# R602X.net
KiCad netlist of a schematic drawn in EAGLE
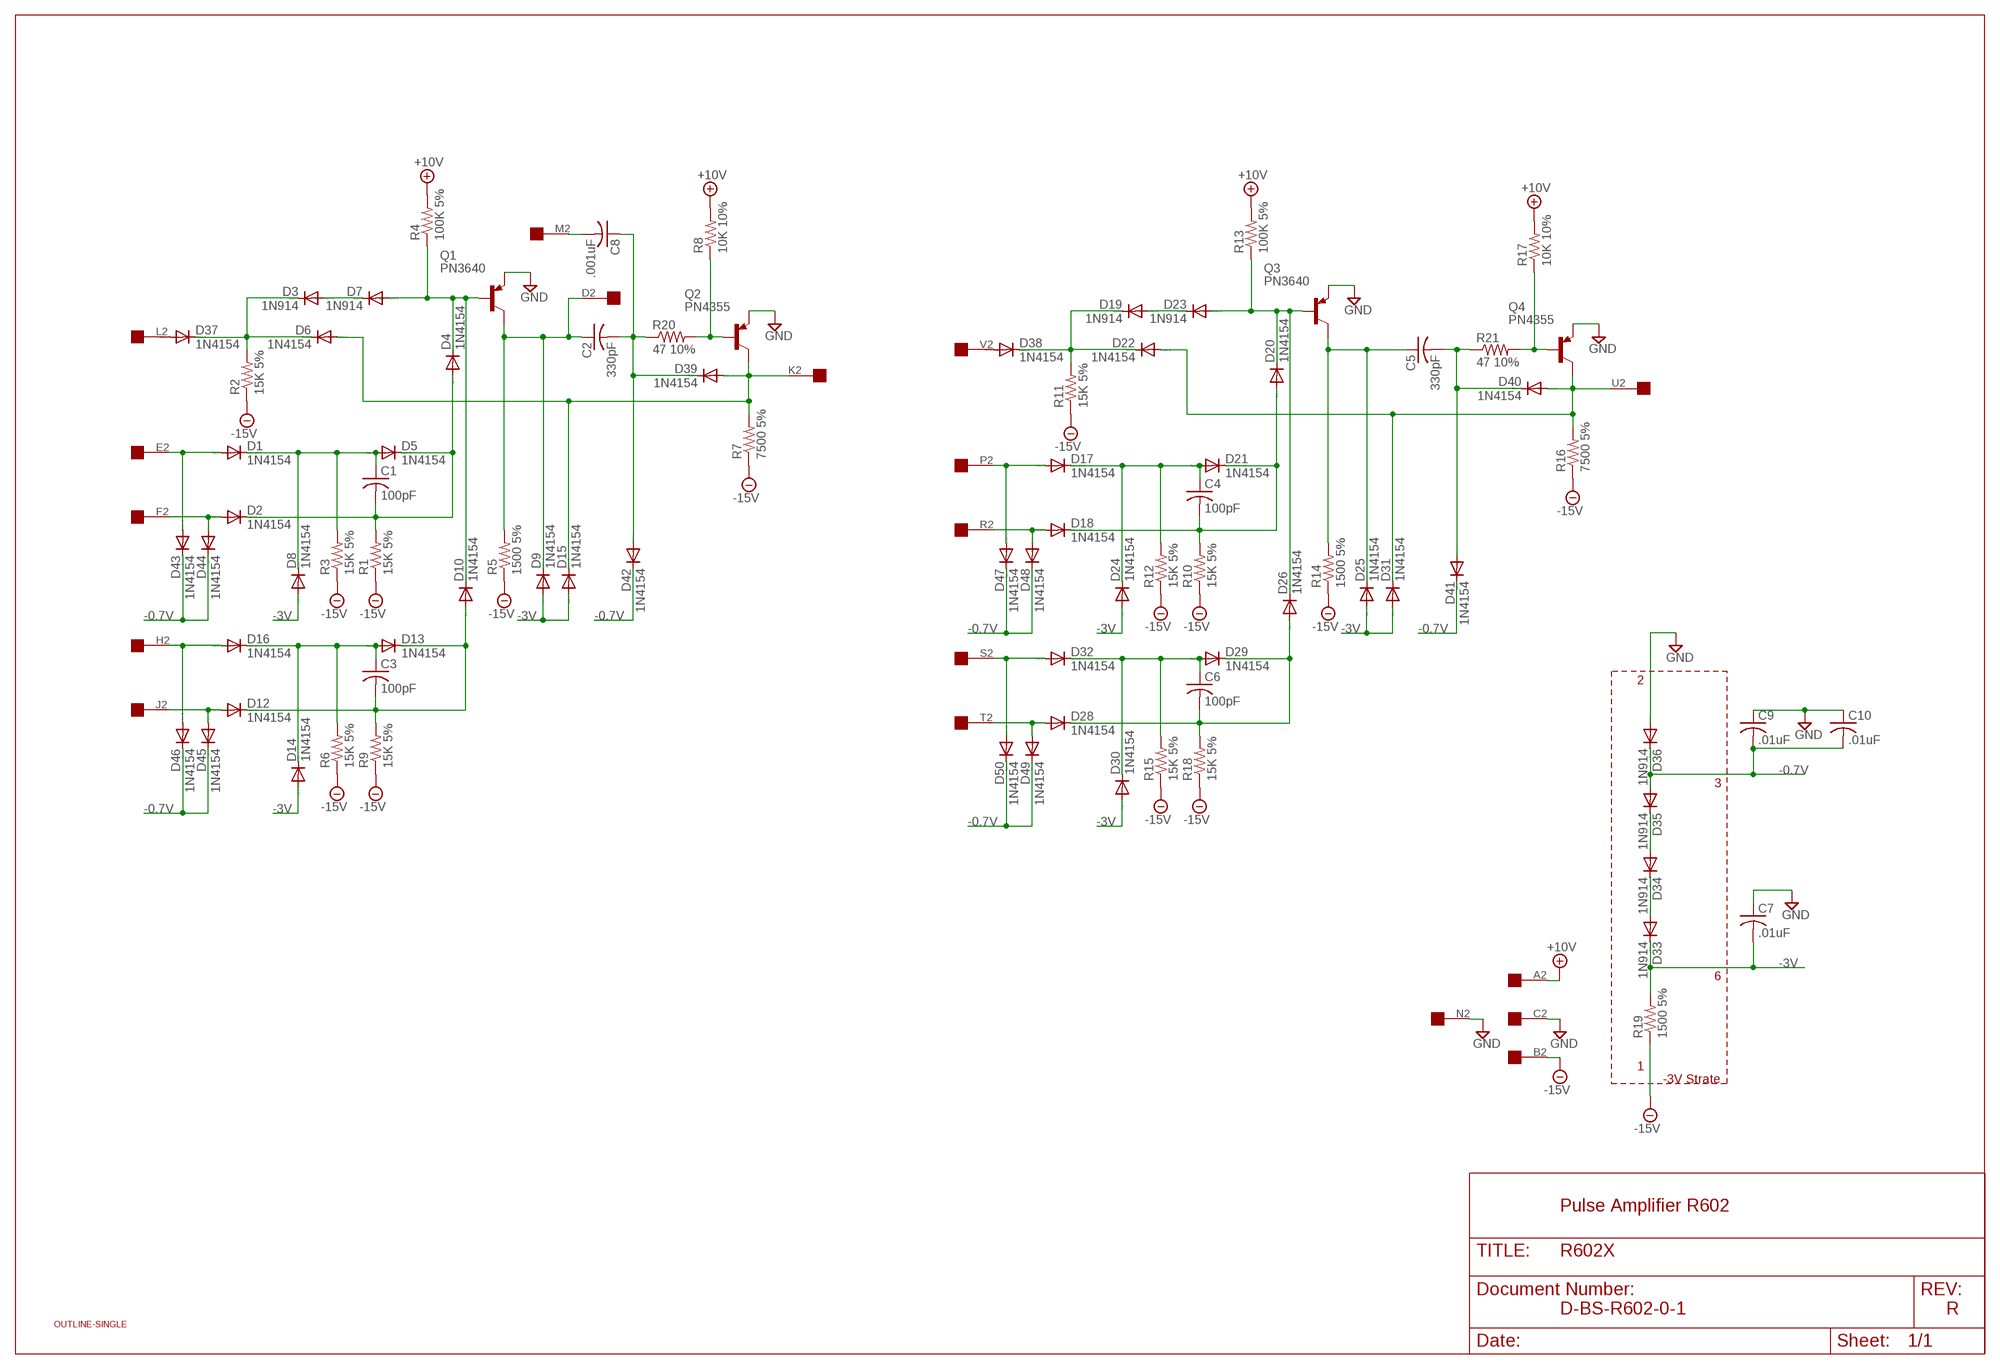
[diagram p0: schematic, sheet 1]

(export (version "E")
  (design (tool "Eeschema 10.0.6"))
  (components
    (comp (ref "C1")
      (value "100pF")
      (footprint "eagle-import:C050-025X075")
      (libsource (lib "eagle-import") (part "C-US050-025X075"))
    )
    (comp (ref "C2")
      (value "330pF")
      (footprint "eagle-import:C050-025X075")
      (libsource (lib "eagle-import") (part "C-US050-025X075"))
    )
    (comp (ref "C3")
      (value "100pF")
      (footprint "eagle-import:C050-025X075")
      (libsource (lib "eagle-import") (part "C-US050-025X075"))
    )
    (comp (ref "C4")
      (value "100pF")
      (footprint "eagle-import:C050-025X075")
      (libsource (lib "eagle-import") (part "C-US050-025X075"))
    )
    (comp (ref "C5")
      (value "330pF")
      (footprint "eagle-import:C050-025X075")
      (libsource (lib "eagle-import") (part "C-US050-025X075"))
    )
    (comp (ref "C6")
      (value "100pF")
      (footprint "eagle-import:C050-025X075")
      (libsource (lib "eagle-import") (part "C-US050-025X075"))
    )
    (comp (ref "C7")
      (value ".01uF")
      (footprint "eagle-import:C075-032X103")
      (libsource (lib "eagle-import") (part "C-US075-032X103"))
    )
    (comp (ref "C8")
      (value ".001uF")
      (footprint "eagle-import:C050-025X075")
      (libsource (lib "eagle-import") (part "C-US050-025X075"))
    )
    (comp (ref "C9")
      (value ".01uF")
      (footprint "eagle-import:C050-025X075")
      (libsource (lib "eagle-import") (part "C-US050-025X075"))
    )
    (comp (ref "C10")
      (value ".01uF")
      (footprint "eagle-import:C050-025X075")
      (libsource (lib "eagle-import") (part "C-US050-025X075"))
    )
    (comp (ref "D1")
      (value "1N4154")
      (footprint "eagle-import:DO35-10")
      (libsource (lib "eagle-import") (part "1N4148DO35-10"))
    )
    (comp (ref "D2")
      (value "1N4154")
      (footprint "eagle-import:DO35-10")
      (libsource (lib "eagle-import") (part "1N4148DO35-10"))
    )
    (comp (ref "D3")
      (value "1N914")
      (footprint "eagle-import:DO35-10")
      (libsource (lib "eagle-import") (part "1N4148DO35-10"))
    )
    (comp (ref "D4")
      (value "1N4154")
      (footprint "eagle-import:DO35-10")
      (libsource (lib "eagle-import") (part "1N4148DO35-10"))
    )
    (comp (ref "D5")
      (value "1N4154")
      (footprint "eagle-import:DO35-10")
      (libsource (lib "eagle-import") (part "1N4148DO35-10"))
    )
    (comp (ref "D6")
      (value "1N4154")
      (footprint "eagle-import:DO35-10")
      (libsource (lib "eagle-import") (part "1N4148DO35-10"))
    )
    (comp (ref "D7")
      (value "1N914")
      (footprint "eagle-import:DO35-10")
      (libsource (lib "eagle-import") (part "1N4148DO35-10"))
    )
    (comp (ref "D8")
      (value "1N4154")
      (footprint "eagle-import:DO35-10")
      (libsource (lib "eagle-import") (part "1N4148DO35-10"))
    )
    (comp (ref "D9")
      (value "1N4154")
      (footprint "eagle-import:DO35-10")
      (libsource (lib "eagle-import") (part "1N4148DO35-10"))
    )
    (comp (ref "D10")
      (value "1N4154")
      (footprint "eagle-import:DO35-10")
      (libsource (lib "eagle-import") (part "1N4148DO35-10"))
    )
    (comp (ref "D12")
      (value "1N4154")
      (footprint "eagle-import:DO35-10")
      (libsource (lib "eagle-import") (part "1N4148DO35-10"))
    )
    (comp (ref "D13")
      (value "1N4154")
      (footprint "eagle-import:DO35-10")
      (libsource (lib "eagle-import") (part "1N4148DO35-10"))
    )
    (comp (ref "D14")
      (value "1N4154")
      (footprint "eagle-import:DO35-10")
      (libsource (lib "eagle-import") (part "1N4148DO35-10"))
    )
    (comp (ref "D15")
      (value "1N4154")
      (footprint "eagle-import:DO35-10")
      (libsource (lib "eagle-import") (part "1N4148DO35-10"))
    )
    (comp (ref "D16")
      (value "1N4154")
      (footprint "eagle-import:DO35-10")
      (libsource (lib "eagle-import") (part "1N4148DO35-10"))
    )
    (comp (ref "D17")
      (value "1N4154")
      (footprint "eagle-import:DO35-10")
      (libsource (lib "eagle-import") (part "1N4148DO35-10"))
    )
    (comp (ref "D18")
      (value "1N4154")
      (footprint "eagle-import:DO35-10")
      (libsource (lib "eagle-import") (part "1N4148DO35-10"))
    )
    (comp (ref "D19")
      (value "1N914")
      (footprint "eagle-import:DO35-10")
      (libsource (lib "eagle-import") (part "1N4148DO35-10"))
    )
    (comp (ref "D20")
      (value "1N4154")
      (footprint "eagle-import:DO35-10")
      (libsource (lib "eagle-import") (part "1N4148DO35-10"))
    )
    (comp (ref "D21")
      (value "1N4154")
      (footprint "eagle-import:DO35-10")
      (libsource (lib "eagle-import") (part "1N4148DO35-10"))
    )
    (comp (ref "D22")
      (value "1N4154")
      (footprint "eagle-import:DO35-10")
      (libsource (lib "eagle-import") (part "1N4148DO35-10"))
    )
    (comp (ref "D23")
      (value "1N914")
      (footprint "eagle-import:DO35-10")
      (libsource (lib "eagle-import") (part "1N4148DO35-10"))
    )
    (comp (ref "D24")
      (value "1N4154")
      (footprint "eagle-import:DO35-10")
      (libsource (lib "eagle-import") (part "1N4148DO35-10"))
    )
    (comp (ref "D25")
      (value "1N4154")
      (footprint "eagle-import:DO35-10")
      (libsource (lib "eagle-import") (part "1N4148DO35-10"))
    )
    (comp (ref "D26")
      (value "1N4154")
      (footprint "eagle-import:DO35-10")
      (libsource (lib "eagle-import") (part "1N4148DO35-10"))
    )
    (comp (ref "D28")
      (value "1N4154")
      (footprint "eagle-import:DO35-10")
      (libsource (lib "eagle-import") (part "1N4148DO35-10"))
    )
    (comp (ref "D29")
      (value "1N4154")
      (footprint "eagle-import:DO35-10")
      (libsource (lib "eagle-import") (part "1N4148DO35-10"))
    )
    (comp (ref "D30")
      (value "1N4154")
      (footprint "eagle-import:DO35-10")
      (libsource (lib "eagle-import") (part "1N4148DO35-10"))
    )
    (comp (ref "D31")
      (value "1N4154")
      (footprint "eagle-import:DO35-10")
      (libsource (lib "eagle-import") (part "1N4148DO35-10"))
    )
    (comp (ref "D32")
      (value "1N4154")
      (footprint "eagle-import:DO35-10")
      (libsource (lib "eagle-import") (part "1N4148DO35-10"))
    )
    (comp (ref "D33")
      (value "1N914")
      (footprint "eagle-import:DO35-10")
      (libsource (lib "eagle-import") (part "1N4148DO35-10"))
    )
    (comp (ref "D34")
      (value "1N914")
      (footprint "eagle-import:DO35-10")
      (libsource (lib "eagle-import") (part "1N4148DO35-10"))
    )
    (comp (ref "D35")
      (value "1N914")
      (footprint "eagle-import:DO35-10")
      (libsource (lib "eagle-import") (part "1N4148DO35-10"))
    )
    (comp (ref "D36")
      (value "1N914")
      (footprint "eagle-import:DO35-10")
      (libsource (lib "eagle-import") (part "1N4148DO35-10"))
    )
    (comp (ref "D37")
      (value "1N4154")
      (footprint "eagle-import:DO35-10")
      (libsource (lib "eagle-import") (part "1N4148DO35-10"))
    )
    (comp (ref "D38")
      (value "1N4154")
      (footprint "eagle-import:DO35-10")
      (libsource (lib "eagle-import") (part "1N4148DO35-10"))
    )
    (comp (ref "D39")
      (value "1N4154")
      (footprint "eagle-import:DO35-10")
      (libsource (lib "eagle-import") (part "1N4148DO35-10"))
    )
    (comp (ref "D40")
      (value "1N4154")
      (footprint "eagle-import:DO35-10")
      (libsource (lib "eagle-import") (part "1N4148DO35-10"))
    )
    (comp (ref "D41")
      (value "1N4154")
      (footprint "eagle-import:DO35-10")
      (libsource (lib "eagle-import") (part "1N4148DO35-10"))
    )
    (comp (ref "D42")
      (value "1N4154")
      (footprint "eagle-import:DO35-10")
      (libsource (lib "eagle-import") (part "1N4148DO35-10"))
    )
    (comp (ref "D43")
      (value "1N4154")
      (footprint "eagle-import:DO35-10")
      (libsource (lib "eagle-import") (part "1N4148DO35-10"))
    )
    (comp (ref "D44")
      (value "1N4154")
      (footprint "eagle-import:DO35-10")
      (libsource (lib "eagle-import") (part "1N4148DO35-10"))
    )
    (comp (ref "D45")
      (value "1N4154")
      (footprint "eagle-import:DO35-10")
      (libsource (lib "eagle-import") (part "1N4148DO35-10"))
    )
    (comp (ref "D46")
      (value "1N4154")
      (footprint "eagle-import:DO35-10")
      (libsource (lib "eagle-import") (part "1N4148DO35-10"))
    )
    (comp (ref "D47")
      (value "1N4154")
      (footprint "eagle-import:DO35-10")
      (libsource (lib "eagle-import") (part "1N4148DO35-10"))
    )
    (comp (ref "D48")
      (value "1N4154")
      (footprint "eagle-import:DO35-10")
      (libsource (lib "eagle-import") (part "1N4148DO35-10"))
    )
    (comp (ref "D49")
      (value "1N4154")
      (footprint "eagle-import:DO35-10")
      (libsource (lib "eagle-import") (part "1N4148DO35-10"))
    )
    (comp (ref "D50")
      (value "1N4154")
      (footprint "eagle-import:DO35-10")
      (libsource (lib "eagle-import") (part "1N4148DO35-10"))
    )
    (comp (ref "Q1")
      (value "PN3640")
      (footprint "eagle-import:TO39")
      (libsource (lib "eagle-import") (part "2N2904"))
    )
    (comp (ref "Q2")
      (value "PN4355")
      (footprint "eagle-import:TO39")
      (libsource (lib "eagle-import") (part "2N2904"))
    )
    (comp (ref "Q3")
      (value "PN3640")
      (footprint "eagle-import:TO39")
      (libsource (lib "eagle-import") (part "2N2904"))
    )
    (comp (ref "Q4")
      (value "PN4355")
      (footprint "eagle-import:TO39")
      (libsource (lib "eagle-import") (part "2N2904"))
    )
    (comp (ref "R1")
      (value "15K 5%")
      (footprint "eagle-import:0207_10")
      (libsource (lib "eagle-import") (part "R-US_0207/10"))
    )
    (comp (ref "R2")
      (value "15K 5%")
      (footprint "eagle-import:0207_10")
      (libsource (lib "eagle-import") (part "R-US_0207/10"))
    )
    (comp (ref "R3")
      (value "15K 5%")
      (footprint "eagle-import:0207_10")
      (libsource (lib "eagle-import") (part "R-US_0207/10"))
    )
    (comp (ref "R4")
      (value "100K 5%")
      (footprint "eagle-import:0207_10")
      (libsource (lib "eagle-import") (part "R-US_0207/10"))
    )
    (comp (ref "R5")
      (value "1500 5%")
      (footprint "eagle-import:0207_10")
      (libsource (lib "eagle-import") (part "R-US_0207/10"))
    )
    (comp (ref "R6")
      (value "15K 5%")
      (footprint "eagle-import:0207_10")
      (libsource (lib "eagle-import") (part "R-US_0207/10"))
    )
    (comp (ref "R7")
      (value "7500 5%")
      (footprint "eagle-import:0207_10")
      (libsource (lib "eagle-import") (part "R-US_0207/10"))
    )
    (comp (ref "R8")
      (value "10K 10%")
      (footprint "eagle-import:0207_10")
      (libsource (lib "eagle-import") (part "R-US_0207/10"))
    )
    (comp (ref "R9")
      (value "15K 5%")
      (footprint "eagle-import:0207_10")
      (libsource (lib "eagle-import") (part "R-US_0207/10"))
    )
    (comp (ref "R10")
      (value "15K 5%")
      (footprint "eagle-import:0207_10")
      (libsource (lib "eagle-import") (part "R-US_0207/10"))
    )
    (comp (ref "R11")
      (value "15K 5%")
      (footprint "eagle-import:0207_10")
      (libsource (lib "eagle-import") (part "R-US_0207/10"))
    )
    (comp (ref "R12")
      (value "15K 5%")
      (footprint "eagle-import:0207_10")
      (libsource (lib "eagle-import") (part "R-US_0207/10"))
    )
    (comp (ref "R13")
      (value "100K 5%")
      (footprint "eagle-import:0207_10")
      (libsource (lib "eagle-import") (part "R-US_0207/10"))
    )
    (comp (ref "R14")
      (value "1500 5%")
      (footprint "eagle-import:0207_10")
      (libsource (lib "eagle-import") (part "R-US_0207/10"))
    )
    (comp (ref "R15")
      (value "15K 5%")
      (footprint "eagle-import:0207_10")
      (libsource (lib "eagle-import") (part "R-US_0207/10"))
    )
    (comp (ref "R16")
      (value "7500 5%")
      (footprint "eagle-import:0207_10")
      (libsource (lib "eagle-import") (part "R-US_0207/10"))
    )
    (comp (ref "R17")
      (value "10K 10%")
      (footprint "eagle-import:0207_10")
      (libsource (lib "eagle-import") (part "R-US_0207/10"))
    )
    (comp (ref "R18")
      (value "15K 5%")
      (footprint "eagle-import:0207_10")
      (libsource (lib "eagle-import") (part "R-US_0207/10"))
    )
    (comp (ref "R19")
      (value "1500 5%")
      (footprint "eagle-import:0207_10")
      (libsource (lib "eagle-import") (part "R-US_0207/10"))
    )
    (comp (ref "R20")
      (value "47 10%")
      (footprint "eagle-import:0207_10")
      (libsource (lib "eagle-import") (part "R-US_0207/10"))
    )
    (comp (ref "R21")
      (value "47 10%")
      (footprint "eagle-import:0207_10")
      (libsource (lib "eagle-import") (part "R-US_0207/10"))
    )
    (comp (ref "U$1")
      (value "OUTLINE-SINGLE")
      (footprint "eagle-import:SINGLE")
      (libsource (lib "eagle-import") (part "OUTLINE-SINGLE"))
    )
    (comp (ref "U$2")
      (value "EDGE-1")
      (footprint "eagle-import:EDGE-CON1")
      (libsource (lib "eagle-import") (part "EDGE-1"))
    )
  )
  (nets
    (net (code "1") (name "+10V") (class "Default")
      (node (ref "R13") (pin "2") (pinfunction "2_2") (pintype "passive"))
      (node (ref "R17") (pin "2") (pinfunction "2_2") (pintype "passive"))
      (node (ref "R4") (pin "2") (pinfunction "2_2") (pintype "passive"))
      (node (ref "R8") (pin "2") (pinfunction "2_2") (pintype "passive"))
      (node (ref "U$2") (pin "A2") (pinfunction "1_A2") (pintype "bidirectional"))
    )
    (net (code "2") (name "-15V") (class "Default")
      (node (ref "R1") (pin "1") (pinfunction "1_1") (pintype "passive"))
      (node (ref "R10") (pin "1") (pinfunction "1_1") (pintype "passive"))
      (node (ref "R11") (pin "1") (pinfunction "1_1") (pintype "passive"))
      (node (ref "R12") (pin "1") (pinfunction "1_1") (pintype "passive"))
      (node (ref "R14") (pin "1") (pinfunction "1_1") (pintype "passive"))
      (node (ref "R15") (pin "1") (pinfunction "1_1") (pintype "passive"))
      (node (ref "R16") (pin "1") (pinfunction "1_1") (pintype "passive"))
      (node (ref "R18") (pin "1") (pinfunction "1_1") (pintype "passive"))
      (node (ref "R19") (pin "1") (pinfunction "1_1") (pintype "passive"))
      (node (ref "R2") (pin "1") (pinfunction "1_1") (pintype "passive"))
      (node (ref "R3") (pin "1") (pinfunction "1_1") (pintype "passive"))
      (node (ref "R5") (pin "1") (pinfunction "1_1") (pintype "passive"))
      (node (ref "R6") (pin "1") (pinfunction "1_1") (pintype "passive"))
      (node (ref "R7") (pin "1") (pinfunction "1_1") (pintype "passive"))
      (node (ref "R9") (pin "1") (pinfunction "1_1") (pintype "passive"))
      (node (ref "U$2") (pin "B2") (pinfunction "1_B2") (pintype "bidirectional"))
    )
    (net (code "3") (name "/-0.7V") (class "Default")
      (node (ref "C10") (pin "2") (pinfunction "2_2") (pintype "passive"))
      (node (ref "C9") (pin "2") (pinfunction "2_2") (pintype "passive"))
      (node (ref "D35") (pin "A") (pinfunction "A_A") (pintype "passive"))
      (node (ref "D36") (pin "C") (pinfunction "C_C") (pintype "passive"))
      (node (ref "D41") (pin "C") (pinfunction "C_C") (pintype "passive"))
      (node (ref "D42") (pin "C") (pinfunction "C_C") (pintype "passive"))
      (node (ref "D43") (pin "C") (pinfunction "C_C") (pintype "passive"))
      (node (ref "D44") (pin "C") (pinfunction "C_C") (pintype "passive"))
      (node (ref "D45") (pin "C") (pinfunction "C_C") (pintype "passive"))
      (node (ref "D46") (pin "C") (pinfunction "C_C") (pintype "passive"))
      (node (ref "D47") (pin "C") (pinfunction "C_C") (pintype "passive"))
      (node (ref "D48") (pin "C") (pinfunction "C_C") (pintype "passive"))
      (node (ref "D49") (pin "C") (pinfunction "C_C") (pintype "passive"))
      (node (ref "D50") (pin "C") (pinfunction "C_C") (pintype "passive"))
    )
    (net (code "4") (name "/-3V") (class "Default")
      (node (ref "C7") (pin "2") (pinfunction "2_2") (pintype "passive"))
      (node (ref "D14") (pin "A") (pinfunction "A_A") (pintype "passive"))
      (node (ref "D15") (pin "A") (pinfunction "A_A") (pintype "passive"))
      (node (ref "D24") (pin "A") (pinfunction "A_A") (pintype "passive"))
      (node (ref "D25") (pin "A") (pinfunction "A_A") (pintype "passive"))
      (node (ref "D30") (pin "A") (pinfunction "A_A") (pintype "passive"))
      (node (ref "D31") (pin "A") (pinfunction "A_A") (pintype "passive"))
      (node (ref "D33") (pin "C") (pinfunction "C_C") (pintype "passive"))
      (node (ref "D8") (pin "A") (pinfunction "A_A") (pintype "passive"))
      (node (ref "D9") (pin "A") (pinfunction "A_A") (pintype "passive"))
      (node (ref "R19") (pin "2") (pinfunction "2_2") (pintype "passive"))
    )
    (net (code "5") (name "GND") (class "Default")
      (node (ref "C10") (pin "1") (pinfunction "1_1") (pintype "passive"))
      (node (ref "C7") (pin "1") (pinfunction "1_1") (pintype "passive"))
      (node (ref "C9") (pin "1") (pinfunction "1_1") (pintype "passive"))
      (node (ref "D36") (pin "A") (pinfunction "A_A") (pintype "passive"))
      (node (ref "Q1") (pin "1") (pinfunction "E_1") (pintype "passive"))
      (node (ref "Q2") (pin "1") (pinfunction "E_1") (pintype "passive"))
      (node (ref "Q3") (pin "1") (pinfunction "E_1") (pintype "passive"))
      (node (ref "Q4") (pin "1") (pinfunction "E_1") (pintype "passive"))
      (node (ref "U$2") (pin "C2") (pinfunction "1_C2") (pintype "bidirectional"))
      (node (ref "U$2") (pin "N2") (pinfunction "1_N2") (pintype "bidirectional"))
    )
    (net (code "6") (name "Net-(C1-Pad1)") (class "Default")
      (node (ref "C1") (pin "1") (pinfunction "1_1") (pintype "passive"))
      (node (ref "D1") (pin "C") (pinfunction "C_C") (pintype "passive"))
      (node (ref "D5") (pin "A") (pinfunction "A_A") (pintype "passive"))
      (node (ref "D8") (pin "C") (pinfunction "C_C") (pintype "passive"))
      (node (ref "R3") (pin "2") (pinfunction "2_2") (pintype "passive"))
    )
    (net (code "7") (name "Net-(C1-Pad2)") (class "Default")
      (node (ref "C1") (pin "2") (pinfunction "2_2") (pintype "passive"))
      (node (ref "D2") (pin "C") (pinfunction "C_C") (pintype "passive"))
      (node (ref "D4") (pin "A") (pinfunction "A_A") (pintype "passive"))
      (node (ref "D5") (pin "C") (pinfunction "C_C") (pintype "passive"))
      (node (ref "R1") (pin "2") (pinfunction "2_2") (pintype "passive"))
    )
    (net (code "8") (name "Net-(C2-Pad2)") (class "Default")
      (node (ref "C2") (pin "2") (pinfunction "2_2") (pintype "passive"))
      (node (ref "C8") (pin "1") (pinfunction "1_1") (pintype "passive"))
      (node (ref "D39") (pin "C") (pinfunction "C_C") (pintype "passive"))
      (node (ref "D42") (pin "A") (pinfunction "A_A") (pintype "passive"))
      (node (ref "R20") (pin "1") (pinfunction "1_1") (pintype "passive"))
    )
    (net (code "9") (name "Net-(C3-Pad1)") (class "Default")
      (node (ref "C3") (pin "1") (pinfunction "1_1") (pintype "passive"))
      (node (ref "D13") (pin "A") (pinfunction "A_A") (pintype "passive"))
      (node (ref "D14") (pin "C") (pinfunction "C_C") (pintype "passive"))
      (node (ref "D16") (pin "C") (pinfunction "C_C") (pintype "passive"))
      (node (ref "R6") (pin "2") (pinfunction "2_2") (pintype "passive"))
    )
    (net (code "10") (name "Net-(C3-Pad2)") (class "Default")
      (node (ref "C3") (pin "2") (pinfunction "2_2") (pintype "passive"))
      (node (ref "D10") (pin "A") (pinfunction "A_A") (pintype "passive"))
      (node (ref "D12") (pin "C") (pinfunction "C_C") (pintype "passive"))
      (node (ref "D13") (pin "C") (pinfunction "C_C") (pintype "passive"))
      (node (ref "R9") (pin "2") (pinfunction "2_2") (pintype "passive"))
    )
    (net (code "11") (name "Net-(C4-Pad1)") (class "Default")
      (node (ref "C4") (pin "1") (pinfunction "1_1") (pintype "passive"))
      (node (ref "D17") (pin "C") (pinfunction "C_C") (pintype "passive"))
      (node (ref "D21") (pin "A") (pinfunction "A_A") (pintype "passive"))
      (node (ref "D24") (pin "C") (pinfunction "C_C") (pintype "passive"))
      (node (ref "R12") (pin "2") (pinfunction "2_2") (pintype "passive"))
    )
    (net (code "12") (name "Net-(C4-Pad2)") (class "Default")
      (node (ref "C4") (pin "2") (pinfunction "2_2") (pintype "passive"))
      (node (ref "D18") (pin "C") (pinfunction "C_C") (pintype "passive"))
      (node (ref "D20") (pin "A") (pinfunction "A_A") (pintype "passive"))
      (node (ref "D21") (pin "C") (pinfunction "C_C") (pintype "passive"))
      (node (ref "R10") (pin "2") (pinfunction "2_2") (pintype "passive"))
    )
    (net (code "13") (name "Net-(C5-Pad2)") (class "Default")
      (node (ref "C5") (pin "2") (pinfunction "2_2") (pintype "passive"))
      (node (ref "D40") (pin "C") (pinfunction "C_C") (pintype "passive"))
      (node (ref "D41") (pin "A") (pinfunction "A_A") (pintype "passive"))
      (node (ref "R21") (pin "1") (pinfunction "1_1") (pintype "passive"))
    )
    (net (code "14") (name "Net-(C6-Pad1)") (class "Default")
      (node (ref "C6") (pin "1") (pinfunction "1_1") (pintype "passive"))
      (node (ref "D29") (pin "A") (pinfunction "A_A") (pintype "passive"))
      (node (ref "D30") (pin "C") (pinfunction "C_C") (pintype "passive"))
      (node (ref "D32") (pin "C") (pinfunction "C_C") (pintype "passive"))
      (node (ref "R15") (pin "2") (pinfunction "2_2") (pintype "passive"))
    )
    (net (code "15") (name "Net-(C6-Pad2)") (class "Default")
      (node (ref "C6") (pin "2") (pinfunction "2_2") (pintype "passive"))
      (node (ref "D26") (pin "A") (pinfunction "A_A") (pintype "passive"))
      (node (ref "D28") (pin "C") (pinfunction "C_C") (pintype "passive"))
      (node (ref "D29") (pin "C") (pinfunction "C_C") (pintype "passive"))
      (node (ref "R18") (pin "2") (pinfunction "2_2") (pintype "passive"))
    )
    (net (code "16") (name "Net-(D3-PadA)") (class "Default")
      (node (ref "D3") (pin "A") (pinfunction "A_A") (pintype "passive"))
      (node (ref "D7") (pin "C") (pinfunction "C_C") (pintype "passive"))
    )
    (net (code "17") (name "Net-(D3-PadC)") (class "Default")
      (node (ref "D3") (pin "C") (pinfunction "C_C") (pintype "passive"))
      (node (ref "D37") (pin "C") (pinfunction "C_C") (pintype "passive"))
      (node (ref "D6") (pin "C") (pinfunction "C_C") (pintype "passive"))
      (node (ref "R2") (pin "2") (pinfunction "2_2") (pintype "passive"))
    )
    (net (code "18") (name "Net-(D19-PadA)") (class "Default")
      (node (ref "D19") (pin "A") (pinfunction "A_A") (pintype "passive"))
      (node (ref "D23") (pin "C") (pinfunction "C_C") (pintype "passive"))
    )
    (net (code "19") (name "Net-(D19-PadC)") (class "Default")
      (node (ref "D19") (pin "C") (pinfunction "C_C") (pintype "passive"))
      (node (ref "D22") (pin "C") (pinfunction "C_C") (pintype "passive"))
      (node (ref "D38") (pin "C") (pinfunction "C_C") (pintype "passive"))
      (node (ref "R11") (pin "2") (pinfunction "2_2") (pintype "passive"))
    )
    (net (code "20") (name "Net-(D33-PadA)") (class "Default")
      (node (ref "D33") (pin "A") (pinfunction "A_A") (pintype "passive"))
      (node (ref "D34") (pin "C") (pinfunction "C_C") (pintype "passive"))
    )
    (net (code "21") (name "Net-(D34-PadA)") (class "Default")
      (node (ref "D34") (pin "A") (pinfunction "A_A") (pintype "passive"))
      (node (ref "D35") (pin "C") (pinfunction "C_C") (pintype "passive"))
    )
    (net (code "22") (name "Net-(Q1-B)") (class "Default")
      (node (ref "D10") (pin "C") (pinfunction "C_C") (pintype "passive"))
      (node (ref "D4") (pin "C") (pinfunction "C_C") (pintype "passive"))
      (node (ref "D7") (pin "A") (pinfunction "A_A") (pintype "passive"))
      (node (ref "Q1") (pin "2") (pinfunction "B_2") (pintype "passive"))
      (node (ref "R4") (pin "1") (pinfunction "1_1") (pintype "passive"))
    )
    (net (code "23") (name "Net-(Q1-C)") (class "Default")
      (node (ref "C2") (pin "1") (pinfunction "1_1") (pintype "passive"))
      (node (ref "D9") (pin "C") (pinfunction "C_C") (pintype "passive"))
      (node (ref "Q1") (pin "3") (pinfunction "C_3") (pintype "passive"))
      (node (ref "R5") (pin "2") (pinfunction "2_2") (pintype "passive"))
      (node (ref "U$2") (pin "D2") (pinfunction "1_D2") (pintype "bidirectional"))
    )
    (net (code "24") (name "Net-(Q2-B)") (class "Default")
      (node (ref "Q2") (pin "2") (pinfunction "B_2") (pintype "passive"))
      (node (ref "R20") (pin "2") (pinfunction "2_2") (pintype "passive"))
      (node (ref "R8") (pin "1") (pinfunction "1_1") (pintype "passive"))
    )
    (net (code "25") (name "Net-(Q2-C)") (class "Default")
      (node (ref "D15") (pin "C") (pinfunction "C_C") (pintype "passive"))
      (node (ref "D39") (pin "A") (pinfunction "A_A") (pintype "passive"))
      (node (ref "D6") (pin "A") (pinfunction "A_A") (pintype "passive"))
      (node (ref "Q2") (pin "3") (pinfunction "C_3") (pintype "passive"))
      (node (ref "R7") (pin "2") (pinfunction "2_2") (pintype "passive"))
      (node (ref "U$2") (pin "K2") (pinfunction "1_K2") (pintype "bidirectional"))
    )
    (net (code "26") (name "Net-(Q3-B)") (class "Default")
      (node (ref "D20") (pin "C") (pinfunction "C_C") (pintype "passive"))
      (node (ref "D23") (pin "A") (pinfunction "A_A") (pintype "passive"))
      (node (ref "D26") (pin "C") (pinfunction "C_C") (pintype "passive"))
      (node (ref "Q3") (pin "2") (pinfunction "B_2") (pintype "passive"))
      (node (ref "R13") (pin "1") (pinfunction "1_1") (pintype "passive"))
    )
    (net (code "27") (name "Net-(Q3-C)") (class "Default")
      (node (ref "C5") (pin "1") (pinfunction "1_1") (pintype "passive"))
      (node (ref "D25") (pin "C") (pinfunction "C_C") (pintype "passive"))
      (node (ref "Q3") (pin "3") (pinfunction "C_3") (pintype "passive"))
      (node (ref "R14") (pin "2") (pinfunction "2_2") (pintype "passive"))
    )
    (net (code "28") (name "Net-(Q4-B)") (class "Default")
      (node (ref "Q4") (pin "2") (pinfunction "B_2") (pintype "passive"))
      (node (ref "R17") (pin "1") (pinfunction "1_1") (pintype "passive"))
      (node (ref "R21") (pin "2") (pinfunction "2_2") (pintype "passive"))
    )
    (net (code "29") (name "Net-(Q4-C)") (class "Default")
      (node (ref "D22") (pin "A") (pinfunction "A_A") (pintype "passive"))
      (node (ref "D31") (pin "C") (pinfunction "C_C") (pintype "passive"))
      (node (ref "D40") (pin "A") (pinfunction "A_A") (pintype "passive"))
      (node (ref "Q4") (pin "3") (pinfunction "C_3") (pintype "passive"))
      (node (ref "R16") (pin "2") (pinfunction "2_2") (pintype "passive"))
      (node (ref "U$2") (pin "U2") (pinfunction "1_U2") (pintype "bidirectional"))
    )
    (net (code "30") (name "Net-(U$2E-1)") (class "Default")
      (node (ref "D1") (pin "A") (pinfunction "A_A") (pintype "passive"))
      (node (ref "D43") (pin "A") (pinfunction "A_A") (pintype "passive"))
      (node (ref "U$2") (pin "E2") (pinfunction "1_E2") (pintype "bidirectional"))
    )
    (net (code "31") (name "Net-(U$2F-1)") (class "Default")
      (node (ref "D2") (pin "A") (pinfunction "A_A") (pintype "passive"))
      (node (ref "D44") (pin "A") (pinfunction "A_A") (pintype "passive"))
      (node (ref "U$2") (pin "F2") (pinfunction "1_F2") (pintype "bidirectional"))
    )
    (net (code "32") (name "Net-(U$2G-1)") (class "Default")
      (node (ref "D16") (pin "A") (pinfunction "A_A") (pintype "passive"))
      (node (ref "D46") (pin "A") (pinfunction "A_A") (pintype "passive"))
      (node (ref "U$2") (pin "H2") (pinfunction "1_H2") (pintype "bidirectional"))
    )
    (net (code "33") (name "Net-(U$2H-1)") (class "Default")
      (node (ref "D12") (pin "A") (pinfunction "A_A") (pintype "passive"))
      (node (ref "D45") (pin "A") (pinfunction "A_A") (pintype "passive"))
      (node (ref "U$2") (pin "J2") (pinfunction "1_J2") (pintype "bidirectional"))
    )
    (net (code "34") (name "Net-(U$2J-1)") (class "Default")
      (node (ref "D37") (pin "A") (pinfunction "A_A") (pintype "passive"))
      (node (ref "U$2") (pin "L2") (pinfunction "1_L2") (pintype "bidirectional"))
    )
    (net (code "35") (name "Net-(U$2K-1)") (class "Default")
      (node (ref "C8") (pin "2") (pinfunction "2_2") (pintype "passive"))
      (node (ref "U$2") (pin "M2") (pinfunction "1_M2") (pintype "bidirectional"))
    )
    (net (code "36") (name "Net-(U$2M-1)") (class "Default")
      (node (ref "D17") (pin "A") (pinfunction "A_A") (pintype "passive"))
      (node (ref "D47") (pin "A") (pinfunction "A_A") (pintype "passive"))
      (node (ref "U$2") (pin "P2") (pinfunction "1_P2") (pintype "bidirectional"))
    )
    (net (code "37") (name "Net-(U$2N-1)") (class "Default")
      (node (ref "D18") (pin "A") (pinfunction "A_A") (pintype "passive"))
      (node (ref "D48") (pin "A") (pinfunction "A_A") (pintype "passive"))
      (node (ref "U$2") (pin "R2") (pinfunction "1_R2") (pintype "bidirectional"))
    )
    (net (code "38") (name "Net-(U$2O-1)") (class "Default")
      (node (ref "D32") (pin "A") (pinfunction "A_A") (pintype "passive"))
      (node (ref "D50") (pin "A") (pinfunction "A_A") (pintype "passive"))
      (node (ref "U$2") (pin "S2") (pinfunction "1_S2") (pintype "bidirectional"))
    )
    (net (code "39") (name "Net-(U$2P-1)") (class "Default")
      (node (ref "D28") (pin "A") (pinfunction "A_A") (pintype "passive"))
      (node (ref "D49") (pin "A") (pinfunction "A_A") (pintype "passive"))
      (node (ref "U$2") (pin "T2") (pinfunction "1_T2") (pintype "bidirectional"))
    )
    (net (code "40") (name "Net-(U$2R-1)") (class "Default")
      (node (ref "D38") (pin "A") (pinfunction "A_A") (pintype "passive"))
      (node (ref "U$2") (pin "V2") (pinfunction "1_V2") (pintype "bidirectional"))
    )
  )
)
